# Main.net
KiCad netlist of a schematic drawn in Altium Designer
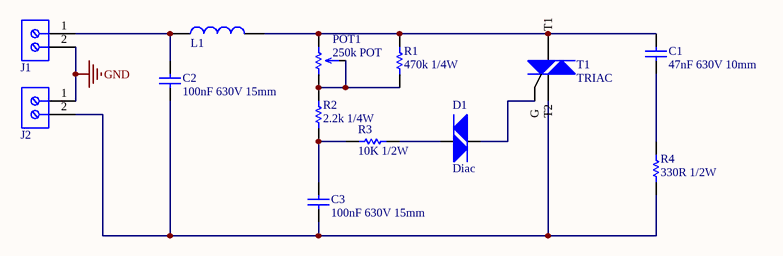
[diagram p0: Main.SchDoc]

(export (version "E")
  (design (tool "Eeschema 10.0.6"))
  (components
    (comp (ref "C1")
      (value "47nF 630V 10mm")
      (footprint "10mm_CAP")
      (description "CAP.POL.47nF 630VDC 10MM 10% MKT FARATRONIC")
      (libsource (lib "Integrated_Library1") (part "47nF 630V 10mm"))
    )
    (comp (ref "C2")
      (value "100nF 630V 15mm")
      (footprint "15mm_cap")
      (description "CAP.POL.100nF 630VDC 15MM 10% MKP DAMLA BULK FARAT")
      (libsource (lib "Integrated_Library1") (part "100nF 630V 15mm"))
    )
    (comp (ref "C3")
      (value "100nF 630V 15mm")
      (footprint "15mm_cap")
      (description "CAP.POL.100nF 630VDC 15MM 10% MKP DAMLA BULK FARAT")
      (libsource (lib "Integrated_Library1") (part "100nF 630V 15mm"))
    )
    (comp (ref "D1")
      (value "Diac")
      (footprint "DB3")
      (description "Diac/Sidac Thyristor 30 ~ 34V DO-35")
      (fields (field (name "MF") "STMicroelectronics") (field (name "MP") "DB3TG"))
      (libsource (lib "Integrated_Library1") (part "DB3"))
    )
    (comp (ref "J1")
      (value "691103110002")
      (footprint "691103110002")
      (description "WR-TBL Series 1031 Horizontal Entry Modular, THT, pitch 3.5mm, 2p")
      (fields (field (name "MANUFACTURER") "Wurth Elektronik"))
      (libsource (lib "WE - Electromechanical Components") (part "TBL - 1R - 02P - Screw"))
    )
    (comp (ref "J2")
      (value "691103110002")
      (footprint "691103110002")
      (description "WR-TBL Series 1031 Horizontal Entry Modular, THT, pitch 3.5mm, 2p")
      (fields (field (name "MANUFACTURER") "Wurth Elektronik"))
      (libsource (lib "WE - Electromechanical Components") (part "TBL - 1R - 02P - Screw"))
    )
    (comp (ref "L1")
      (value "90µH")
      (footprint "7447013")
      (description "WE-FI THT Leaded Toroidal Line Choke, 90µH, 4.6A, 0.04Ω")
      (fields
        (field (name "MANUFACTURER PART NUMBER") "7447013")
        (field (name "MANUFACTURER") "Wurth Elektronik")
      )
      (libsource (lib "Integrated_Library1") (part "90uH Toroidal Line Choke"))
    )
    (comp (ref "POT1")
      (value "250k POT")
      (footprint "Potentiometers")
      (description "POT 220K 0.125W 1 TURN CARBON LINEAR ±20%")
      (libsource (lib "Integrated_Library1") (part "Potentiometer"))
    )
    (comp (ref "R1")
      (value "470k 1/4W")
      (footprint "1/4W axial")
      (description "407 1/4W axial resistor")
      (libsource (lib "Integrated_Library1") (part "470K 1/4W axial"))
    )
    (comp (ref "R2")
      (value "2.2k 1/4W")
      (footprint "1/4W axial")
      (description "2.2K axial resistor")
      (libsource (lib "Integrated_Library1") (part "2.2K 1/24 axial"))
    )
    (comp (ref "R3")
      (value "10K 1/2W")
      (footprint "1/4W axial")
      (description "10K 1/4W resistor")
      (libsource (lib "Integrated_Library1") (part "10K 1/2W axial"))
    )
    (comp (ref "R4")
      (value "330R 1/2W")
      (footprint "1/2 axial")
      (description "330R 1/2W axial")
      (libsource (lib "Integrated_Library1") (part "330R 1/2W axial"))
    )
    (comp (ref "T1")
      (value "TRIAC")
      (footprint "TO-220")
      (description "TRIAC Standard 800 V XA Through Hole TO-220AB")
      (libsource (lib "Integrated_Library1") (part "TRIAC"))
    )
  )
  (nets
    (net (code "1") (name "GND") (class "Default")
      (node (ref "J1") (pin "2") (pinfunction "2_2") (pintype "passive"))
      (node (ref "J2") (pin "1") (pinfunction "1_1") (pintype "passive"))
    )
    (net (code "2") (name "Net-(C1-Pad1)") (class "Default")
      (node (ref "C1") (pin "1") (pinfunction "1_1") (pintype "passive"))
      (node (ref "R4") (pin "1") (pinfunction "1_1") (pintype "passive"))
    )
    (net (code "3") (name "Net-(C2-Pad2)") (class "Default")
      (node (ref "C2") (pin "2") (pinfunction "2_2") (pintype "passive"))
      (node (ref "J1") (pin "1") (pinfunction "1_1") (pintype "passive"))
      (node (ref "L1") (pin "1") (pinfunction "1_1") (pintype "passive"))
    )
    (net (code "4") (name "Net-(C3-Pad2)") (class "Default")
      (node (ref "C3") (pin "2") (pinfunction "2_2") (pintype "passive"))
      (node (ref "R2") (pin "2") (pinfunction "2_2") (pintype "passive"))
      (node (ref "R3") (pin "2") (pinfunction "2_2") (pintype "passive"))
    )
    (net (code "5") (name "Net-(D1-Pad1)") (class "Default")
      (node (ref "D1") (pin "1") (pinfunction "1_1") (pintype "passive"))
      (node (ref "R3") (pin "1") (pinfunction "1_1") (pintype "passive"))
    )
    (net (code "6") (name "Net-(POT1-Pad2)") (class "Default")
      (node (ref "POT1") (pin "2") (pinfunction "2_2") (pintype "passive"))
      (node (ref "POT1") (pin "3") (pinfunction "3_3") (pintype "passive"))
      (node (ref "R1") (pin "2") (pinfunction "2_2") (pintype "passive"))
      (node (ref "R2") (pin "1") (pinfunction "1_1") (pintype "passive"))
    )
    (net (code "7") (name "Net-(T1-G)") (class "Default")
      (node (ref "D1") (pin "2") (pinfunction "2_2") (pintype "passive"))
      (node (ref "T1") (pin "3") (pinfunction "G_3") (pintype "passive"))
    )
    (net (code "8") (name "Net-(T1-T1)") (class "Default")
      (node (ref "C1") (pin "2") (pinfunction "2_2") (pintype "passive"))
      (node (ref "L1") (pin "2") (pinfunction "2_2") (pintype "passive"))
      (node (ref "POT1") (pin "1") (pinfunction "1_1") (pintype "passive"))
      (node (ref "R1") (pin "1") (pinfunction "1_1") (pintype "passive"))
      (node (ref "T1") (pin "1") (pinfunction "T1_1") (pintype "passive"))
    )
    (net (code "9") (name "Net-(T1-T2)") (class "Default")
      (node (ref "C2") (pin "1") (pinfunction "1_1") (pintype "passive"))
      (node (ref "C3") (pin "1") (pinfunction "1_1") (pintype "passive"))
      (node (ref "J2") (pin "2") (pinfunction "2_2") (pintype "passive"))
      (node (ref "R4") (pin "2") (pinfunction "2_2") (pintype "passive"))
      (node (ref "T1") (pin "2") (pinfunction "T2_2") (pintype "passive"))
    )
  )
)
